# Analog_Modulation.net
KiCad netlist of a schematic drawn in Altium Designer
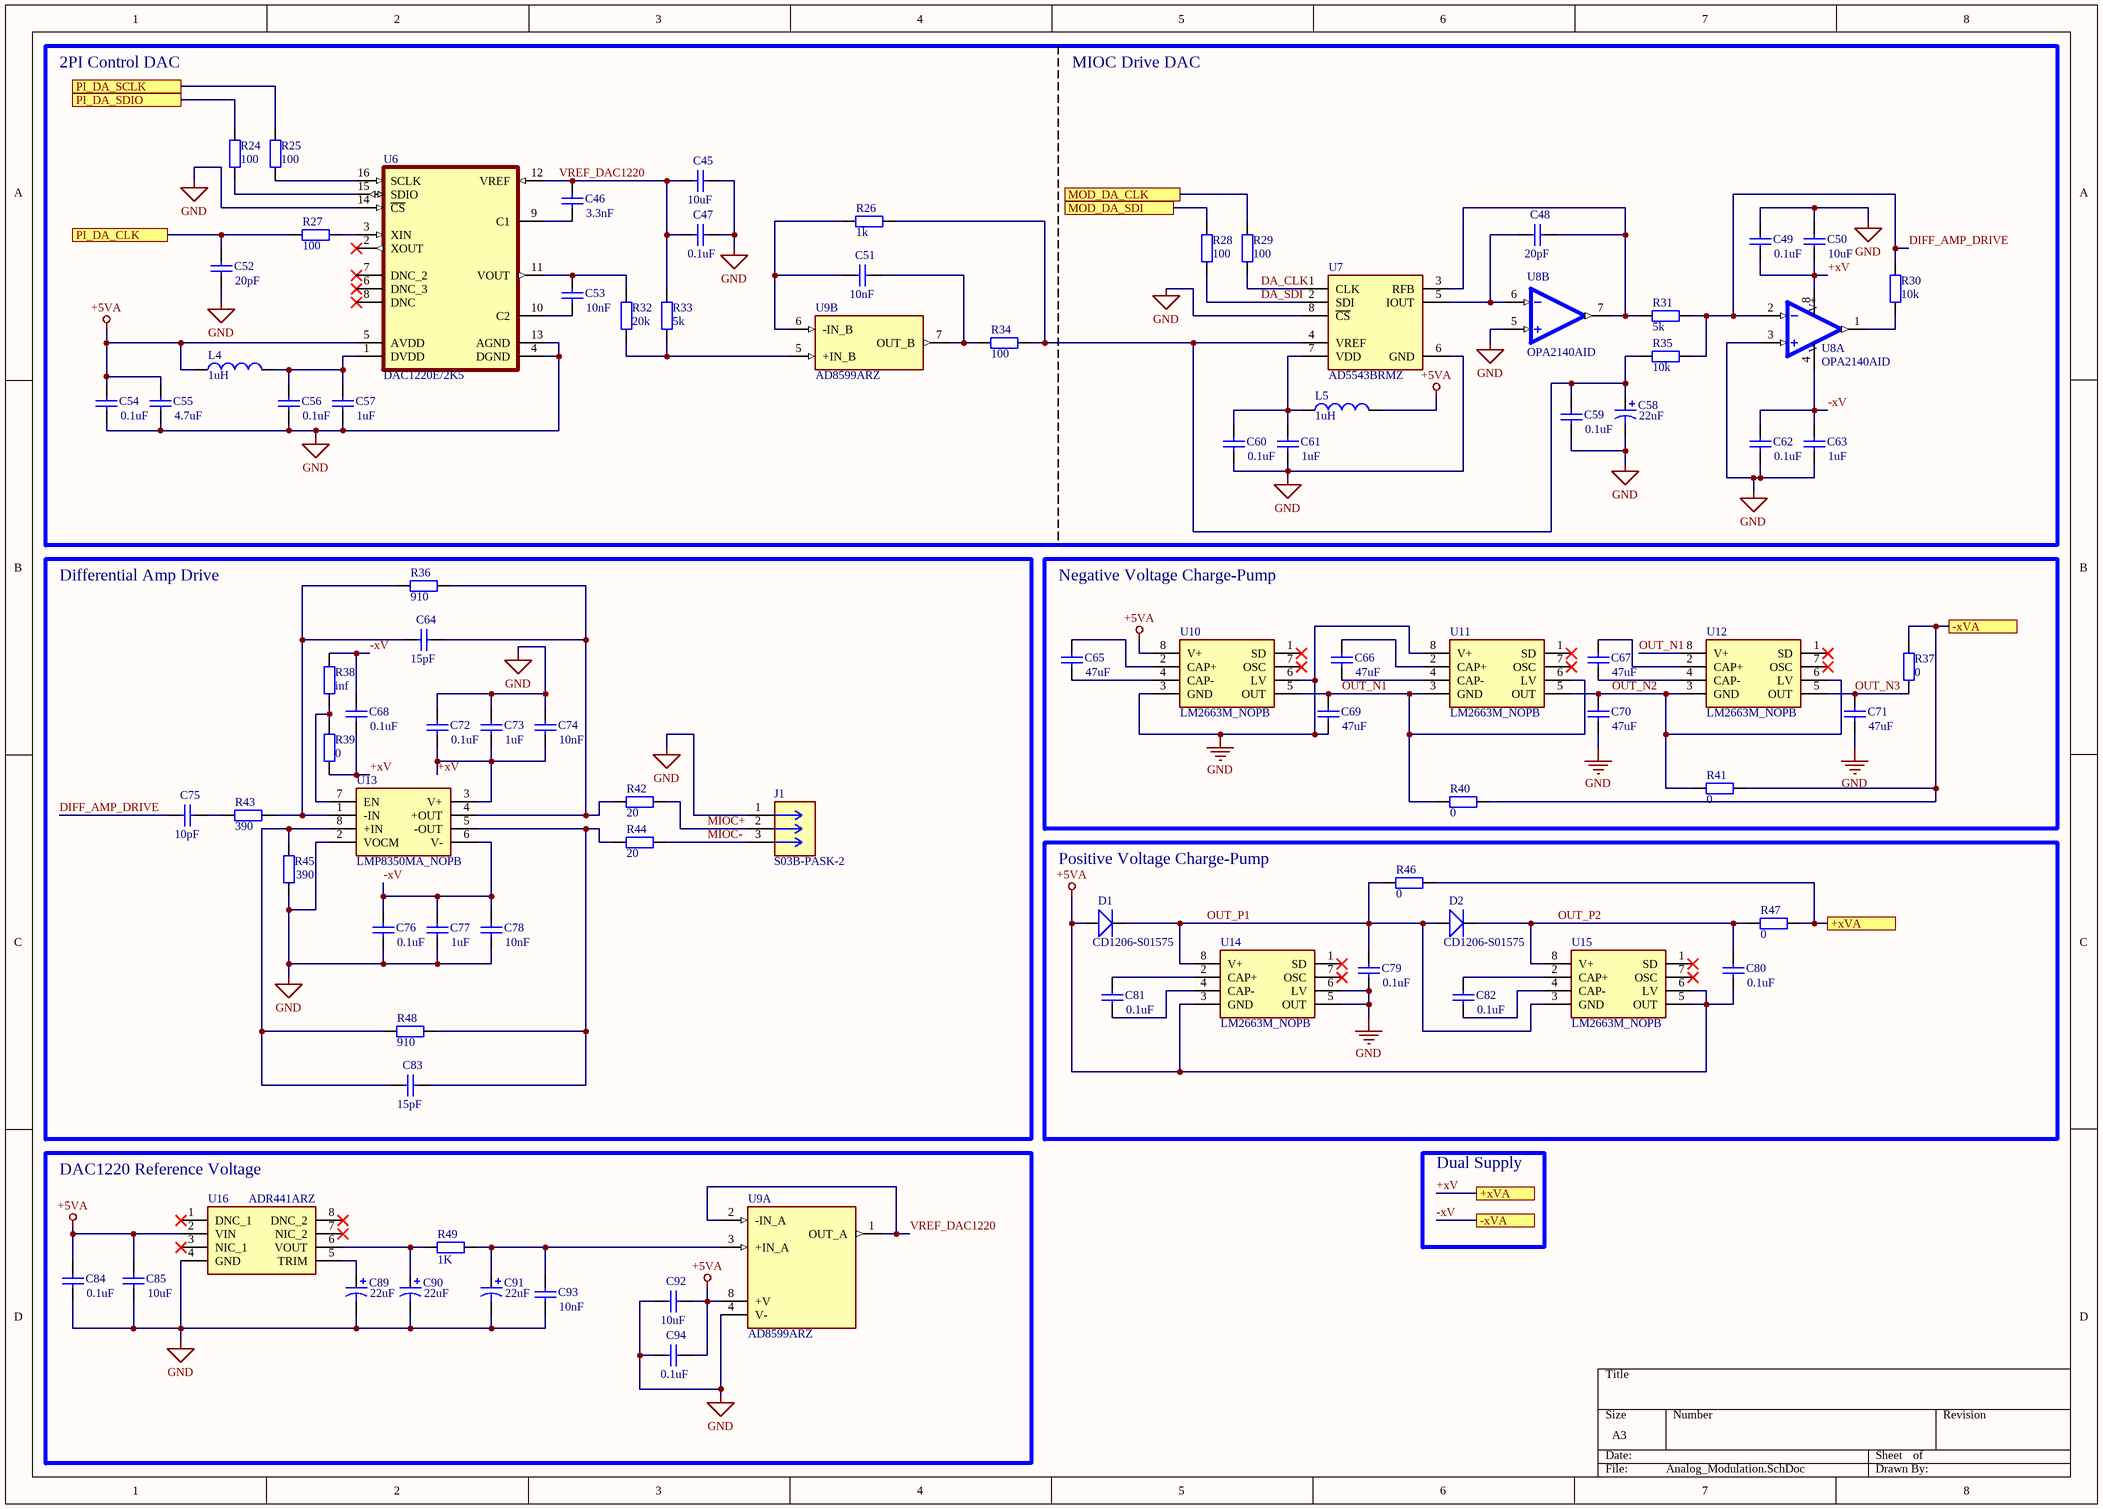
[diagram p0: Analog_Modulation.SchDoc]

(export (version "E")
  (design (tool "Eeschema 10.0.6"))
  (components
    (comp (ref "C45")
      (value "10uF")
      (footprint "CC_0805")
      (description "Capacitor")
      (fields (field (name "Comment") "Cap") (field (name "PUBLISHER") "Altium Limited"))
      (libsource (lib "Miscellaneous Devices") (part "Cap"))
    )
    (comp (ref "C46")
      (value "3.3nF")
      (footprint "CC_0805")
      (description "Capacitor")
      (fields (field (name "Comment") "Cap") (field (name "PUBLISHER") "Altium Limited"))
      (libsource (lib "Miscellaneous Devices") (part "Cap"))
    )
    (comp (ref "C47")
      (value "0.1uF")
      (footprint "CC_0805")
      (description "Capacitor")
      (fields (field (name "Comment") "Cap") (field (name "PUBLISHER") "Altium Limited"))
      (libsource (lib "Miscellaneous Devices") (part "Cap"))
    )
    (comp (ref "C48")
      (value "20pF")
      (footprint "CC_0805")
      (description "Capacitor")
      (fields (field (name "Comment") "Cap") (field (name "PUBLISHER") "Altium Limited"))
      (libsource (lib "Miscellaneous Devices") (part "Cap"))
    )
    (comp (ref "C49")
      (value "0.1uF")
      (footprint "CC_0805")
      (description "Capacitor")
      (fields (field (name "Comment") "Cap") (field (name "PUBLISHER") "Altium Limited"))
      (libsource (lib "Miscellaneous Devices") (part "Cap"))
    )
    (comp (ref "C50")
      (value "10uF")
      (footprint "CC_0805")
      (description "Capacitor")
      (fields (field (name "Comment") "Cap") (field (name "PUBLISHER") "Altium Limited"))
      (libsource (lib "Miscellaneous Devices") (part "Cap"))
    )
    (comp (ref "C51")
      (value "10nF")
      (footprint "CC_0805")
      (description "Capacitor")
      (fields (field (name "Comment") "Cap") (field (name "PUBLISHER") "Altium Limited"))
      (libsource (lib "Miscellaneous Devices") (part "Cap"))
    )
    (comp (ref "C52")
      (value "20pF")
      (footprint "CC_0805")
      (description "Capacitor")
      (fields (field (name "Comment") "Cap") (field (name "PUBLISHER") "Altium Limited"))
      (libsource (lib "Miscellaneous Devices") (part "Cap"))
    )
    (comp (ref "C53")
      (value "10nF")
      (footprint "CC_0805")
      (description "Capacitor")
      (fields (field (name "Comment") "Cap") (field (name "PUBLISHER") "Altium Limited"))
      (libsource (lib "Miscellaneous Devices") (part "Cap"))
    )
    (comp (ref "C54")
      (value "0.1uF")
      (footprint "CC_0805")
      (description "Capacitor")
      (fields (field (name "Comment") "Cap") (field (name "PUBLISHER") "Altium Limited"))
      (libsource (lib "Miscellaneous Devices") (part "Cap"))
    )
    (comp (ref "C55")
      (value "4.7uF")
      (footprint "CC_0805")
      (description "Capacitor")
      (fields (field (name "Comment") "Cap") (field (name "PUBLISHER") "Altium Limited"))
      (libsource (lib "Miscellaneous Devices") (part "Cap"))
    )
    (comp (ref "C56")
      (value "0.1uF")
      (footprint "CC_0805")
      (description "Capacitor")
      (fields (field (name "Comment") "Cap") (field (name "PUBLISHER") "Altium Limited"))
      (libsource (lib "Miscellaneous Devices") (part "Cap"))
    )
    (comp (ref "C57")
      (value "1uF")
      (footprint "CC_0805")
      (description "Capacitor")
      (fields (field (name "Comment") "Cap") (field (name "PUBLISHER") "Altium Limited"))
      (libsource (lib "Miscellaneous Devices") (part "Cap"))
    )
    (comp (ref "C58")
      (value "22uF")
      (footprint "CC_0805")
      (description "Polarized Capacitor (Radial)")
      (fields (field (name "Comment") "Cap Pol1") (field (name "PUBLISHER") "Altium Limited"))
      (libsource (lib "Miscellaneous Devices") (part "Cap Pol1"))
    )
    (comp (ref "C59")
      (value "0.1uF")
      (footprint "CC_0805")
      (description "Capacitor")
      (fields (field (name "Comment") "Cap") (field (name "PUBLISHER") "Altium Limited"))
      (libsource (lib "Miscellaneous Devices") (part "Cap"))
    )
    (comp (ref "C60")
      (value "0.1uF")
      (footprint "CC_0805")
      (description "Capacitor")
      (fields (field (name "Comment") "Cap") (field (name "PUBLISHER") "Altium Limited"))
      (libsource (lib "Miscellaneous Devices") (part "Cap"))
    )
    (comp (ref "C61")
      (value "1uF")
      (footprint "CC_0805")
      (description "Capacitor")
      (fields (field (name "Comment") "Cap") (field (name "PUBLISHER") "Altium Limited"))
      (libsource (lib "Miscellaneous Devices") (part "Cap"))
    )
    (comp (ref "C62")
      (value "0.1uF")
      (footprint "CC_0805")
      (description "Capacitor")
      (fields (field (name "Comment") "Cap") (field (name "PUBLISHER") "Altium Limited"))
      (libsource (lib "Miscellaneous Devices") (part "Cap"))
    )
    (comp (ref "C63")
      (value "1uF")
      (footprint "CC_0805")
      (description "Capacitor")
      (fields (field (name "Comment") "Cap") (field (name "PUBLISHER") "Altium Limited"))
      (libsource (lib "Miscellaneous Devices") (part "Cap"))
    )
    (comp (ref "C64")
      (value "15pF")
      (footprint "CC_0805")
      (description "Capacitor")
      (fields (field (name "Comment") "Cap") (field (name "PUBLISHER") "Altium Limited"))
      (libsource (lib "Miscellaneous Devices") (part "Cap"))
    )
    (comp (ref "C65")
      (value "47uF")
      (footprint "CC_0805")
      (description "Capacitor")
      (fields (field (name "Comment") "Cap") (field (name "PUBLISHER") "Altium Limited"))
      (libsource (lib "Miscellaneous Devices") (part "Cap"))
    )
    (comp (ref "C66")
      (value "47uF")
      (footprint "CC_0805")
      (description "Capacitor")
      (fields (field (name "Comment") "Cap") (field (name "PUBLISHER") "Altium Limited"))
      (libsource (lib "Miscellaneous Devices") (part "Cap"))
    )
    (comp (ref "C67")
      (value "47uF")
      (footprint "CC_0805")
      (description "Capacitor")
      (fields (field (name "Comment") "Cap") (field (name "PUBLISHER") "Altium Limited"))
      (libsource (lib "Miscellaneous Devices") (part "Cap"))
    )
    (comp (ref "C68")
      (value "0.1uF")
      (footprint "CC_0805")
      (description "Capacitor")
      (fields (field (name "Comment") "Cap") (field (name "PUBLISHER") "Altium Limited"))
      (libsource (lib "Miscellaneous Devices") (part "Cap"))
    )
    (comp (ref "C69")
      (value "47uF")
      (footprint "CC_0805")
      (description "Capacitor")
      (fields (field (name "Comment") "Cap") (field (name "PUBLISHER") "Altium Limited"))
      (libsource (lib "Miscellaneous Devices") (part "Cap"))
    )
    (comp (ref "C70")
      (value "47uF")
      (footprint "CC_0805")
      (description "Capacitor")
      (fields (field (name "Comment") "Cap") (field (name "PUBLISHER") "Altium Limited"))
      (libsource (lib "Miscellaneous Devices") (part "Cap"))
    )
    (comp (ref "C71")
      (value "47uF")
      (footprint "CC_0805")
      (description "Capacitor")
      (fields (field (name "Comment") "Cap") (field (name "PUBLISHER") "Altium Limited"))
      (libsource (lib "Miscellaneous Devices") (part "Cap"))
    )
    (comp (ref "C72")
      (value "0.1uF")
      (footprint "CC_0805")
      (description "Capacitor")
      (fields (field (name "Comment") "Cap") (field (name "PUBLISHER") "Altium Limited"))
      (libsource (lib "Miscellaneous Devices") (part "Cap"))
    )
    (comp (ref "C73")
      (value "1uF")
      (footprint "CC_0805")
      (description "Capacitor")
      (fields (field (name "Comment") "Cap") (field (name "PUBLISHER") "Altium Limited"))
      (libsource (lib "Miscellaneous Devices") (part "Cap"))
    )
    (comp (ref "C74")
      (value "10nF")
      (footprint "CC_0805")
      (description "Capacitor")
      (fields (field (name "Comment") "Cap") (field (name "PUBLISHER") "Altium Limited"))
      (libsource (lib "Miscellaneous Devices") (part "Cap"))
    )
    (comp (ref "C75")
      (value "10pF")
      (footprint "CC_0805")
      (description "Capacitor")
      (fields (field (name "Comment") "Cap") (field (name "PUBLISHER") "Altium Limited"))
      (libsource (lib "Miscellaneous Devices") (part "Cap"))
    )
    (comp (ref "C76")
      (value "0.1uF")
      (footprint "CC_0805")
      (description "Capacitor")
      (fields (field (name "Comment") "Cap") (field (name "PUBLISHER") "Altium Limited"))
      (libsource (lib "Miscellaneous Devices") (part "Cap"))
    )
    (comp (ref "C77")
      (value "1uF")
      (footprint "CC_0805")
      (description "Capacitor")
      (fields (field (name "Comment") "Cap") (field (name "PUBLISHER") "Altium Limited"))
      (libsource (lib "Miscellaneous Devices") (part "Cap"))
    )
    (comp (ref "C78")
      (value "10nF")
      (footprint "CC_0805")
      (description "Capacitor")
      (fields (field (name "Comment") "Cap") (field (name "PUBLISHER") "Altium Limited"))
      (libsource (lib "Miscellaneous Devices") (part "Cap"))
    )
    (comp (ref "C79")
      (value "0.1uF")
      (footprint "CC_0805")
      (description "Capacitor")
      (fields (field (name "Comment") "Cap") (field (name "PUBLISHER") "Altium Limited"))
      (libsource (lib "Miscellaneous Devices") (part "Cap"))
    )
    (comp (ref "C80")
      (value "0.1uF")
      (footprint "CC_0805")
      (description "Capacitor")
      (fields (field (name "Comment") "Cap") (field (name "PUBLISHER") "Altium Limited"))
      (libsource (lib "Miscellaneous Devices") (part "Cap"))
    )
    (comp (ref "C81")
      (value "0.1uF")
      (footprint "CC_0805")
      (description "Capacitor")
      (fields (field (name "Comment") "Cap") (field (name "PUBLISHER") "Altium Limited"))
      (libsource (lib "Miscellaneous Devices") (part "Cap"))
    )
    (comp (ref "C82")
      (value "0.1uF")
      (footprint "CC_0805")
      (description "Capacitor")
      (fields (field (name "Comment") "Cap") (field (name "PUBLISHER") "Altium Limited"))
      (libsource (lib "Miscellaneous Devices") (part "Cap"))
    )
    (comp (ref "C83")
      (value "15pF")
      (footprint "CC_0805")
      (description "Capacitor")
      (fields (field (name "Comment") "Cap") (field (name "PUBLISHER") "Altium Limited"))
      (libsource (lib "Miscellaneous Devices") (part "Cap"))
    )
    (comp (ref "C84")
      (value "0.1uF")
      (footprint "CC_0805")
      (description "Capacitor")
      (fields (field (name "Comment") "Cap") (field (name "PUBLISHER") "Altium Limited"))
      (libsource (lib "Miscellaneous Devices") (part "Cap"))
    )
    (comp (ref "C85")
      (value "10uF")
      (footprint "CC_0805")
      (description "Capacitor")
      (fields (field (name "Comment") "Cap") (field (name "PUBLISHER") "Altium Limited"))
      (libsource (lib "Miscellaneous Devices") (part "Cap"))
    )
    (comp (ref "C89")
      (value "22uF")
      (footprint "CC_0805")
      (description "Polarized Capacitor (Radial)")
      (fields (field (name "Comment") "Cap Pol1") (field (name "PUBLISHER") "Altium Limited"))
      (libsource (lib "Miscellaneous Devices") (part "Cap Pol1"))
    )
    (comp (ref "C90")
      (value "22uF")
      (footprint "CC_0805")
      (description "Polarized Capacitor (Radial)")
      (fields (field (name "Comment") "Cap Pol1") (field (name "PUBLISHER") "Altium Limited"))
      (libsource (lib "Miscellaneous Devices") (part "Cap Pol1"))
    )
    (comp (ref "C91")
      (value "22uF")
      (footprint "CC_0805")
      (description "Polarized Capacitor (Radial)")
      (fields (field (name "Comment") "Cap Pol1") (field (name "PUBLISHER") "Altium Limited"))
      (libsource (lib "Miscellaneous Devices") (part "Cap Pol1"))
    )
    (comp (ref "C92")
      (value "10uF")
      (footprint "CC_0805")
      (description "Capacitor")
      (fields (field (name "Comment") "Cap") (field (name "PUBLISHER") "Altium Limited"))
      (libsource (lib "Miscellaneous Devices") (part "Cap"))
    )
    (comp (ref "C93")
      (value "10nF")
      (footprint "CC_0805")
      (description "Capacitor")
      (fields (field (name "Comment") "Cap") (field (name "PUBLISHER") "Altium Limited"))
      (libsource (lib "Miscellaneous Devices") (part "Cap"))
    )
    (comp (ref "C94")
      (value "0.1uF")
      (footprint "CC_0805")
      (description "Capacitor")
      (fields (field (name "Comment") "Cap") (field (name "PUBLISHER") "Altium Limited"))
      (libsource (lib "Miscellaneous Devices") (part "Cap"))
    )
    (comp (ref "D1")
      (value "CD1206-S01575")
      (footprint "LED-1206")
      (description "CD1206-S01575, SMT Switching Diode, Vr=75V 150mA, 4ns, 2-Pin 1206 ¦ Bourns CD1206-S01575")
      (fields (field (name "MF") "Bourns"))
      (libsource (lib "Lib_Schematic_Gyro_Single_Axis") (part "CD1206-S01575"))
    )
    (comp (ref "D2")
      (value "CD1206-S01575")
      (footprint "LED-1206")
      (description "CD1206-S01575, SMT Switching Diode, Vr=75V 150mA, 4ns, 2-Pin 1206 ¦ Bourns CD1206-S01575")
      (fields (field (name "MF") "Bourns"))
      (libsource (lib "Lib_Schematic_Gyro_Single_Axis") (part "CD1206-S01575"))
    )
    (comp (ref "J1")
      (value "S03B-PASK-2")
      (footprint "S03B-PASK-2")
      (description "Headers R/A PCB HDR 3P TIN FRICTION LOCK ¦ Molex Incorporated 22-05-3031")
      (fields (field (name "MF") "Molex") (field (name "MP") "22-05-3031"))
      (libsource (lib "Lib_Schematic_IFOG_Interrogator") (part "S03B-PASK-2"))
    )
    (comp (ref "L4")
      (value "1uH")
      (footprint "WE-PMI_0805_H0.5")
      (description "Inductor")
      (fields (field (name "PUBLISHER") "Altium Limited"))
      (libsource (lib "Miscellaneous Devices") (part "Inductor"))
    )
    (comp (ref "L5")
      (value "1uH")
      (footprint "WE-PMI_0805_H0.5")
      (description "Inductor")
      (fields (field (name "PUBLISHER") "Altium Limited"))
      (libsource (lib "Miscellaneous Devices") (part "Inductor"))
    )
    (comp (ref "R24")
      (value "100")
      (footprint "RR_1220")
      (description "Resistor")
      (fields (field (name "Comment") "Res2") (field (name "PUBLISHER") "Altium Limited"))
      (libsource (lib "") (part "Res2_1"))
    )
    (comp (ref "R25")
      (value "100")
      (footprint "RR_1220")
      (description "Resistor")
      (fields (field (name "Comment") "Res2") (field (name "PUBLISHER") "Altium Limited"))
      (libsource (lib "") (part "Res2_1"))
    )
    (comp (ref "R26")
      (value "1k")
      (footprint "RR_1220")
      (description "Resistor")
      (fields (field (name "Comment") "Res2") (field (name "PUBLISHER") "Altium Limited"))
      (libsource (lib "Miscellaneous Devices") (part "Res2"))
    )
    (comp (ref "R27")
      (value "100")
      (footprint "RR_1220")
      (description "Resistor")
      (fields (field (name "Comment") "Res2") (field (name "PUBLISHER") "Altium Limited"))
      (libsource (lib "Miscellaneous Devices") (part "Res2"))
    )
    (comp (ref "R28")
      (value "100")
      (footprint "RR_1220")
      (description "Resistor")
      (fields (field (name "Comment") "Res2") (field (name "PUBLISHER") "Altium Limited"))
      (libsource (lib "") (part "Res2_3"))
    )
    (comp (ref "R29")
      (value "100")
      (footprint "RR_1220")
      (description "Resistor")
      (fields (field (name "Comment") "Res2") (field (name "PUBLISHER") "Altium Limited"))
      (libsource (lib "") (part "Res2_3"))
    )
    (comp (ref "R30")
      (value "10k")
      (footprint "RR_1220")
      (description "Resistor")
      (fields (field (name "Comment") "Res2") (field (name "PUBLISHER") "Altium Limited"))
      (libsource (lib "") (part "Res2_3"))
    )
    (comp (ref "R31")
      (value "5k")
      (footprint "RR_1220")
      (description "Resistor")
      (fields (field (name "Comment") "Res2") (field (name "PUBLISHER") "Altium Limited"))
      (libsource (lib "Miscellaneous Devices") (part "Res2"))
    )
    (comp (ref "R32")
      (value "20k")
      (footprint "RR_1220")
      (description "Resistor")
      (fields (field (name "Comment") "Res2") (field (name "PUBLISHER") "Altium Limited"))
      (libsource (lib "") (part "Res2_1"))
    )
    (comp (ref "R33")
      (value "5k")
      (footprint "RR_1220")
      (description "Resistor")
      (fields (field (name "Comment") "Res2") (field (name "PUBLISHER") "Altium Limited"))
      (libsource (lib "") (part "Res2_1"))
    )
    (comp (ref "R34")
      (value "100")
      (footprint "RR_1220")
      (description "Resistor")
      (fields (field (name "Comment") "Res2") (field (name "PUBLISHER") "Altium Limited"))
      (libsource (lib "Miscellaneous Devices") (part "Res2"))
    )
    (comp (ref "R35")
      (value "10k")
      (footprint "RR_1220")
      (description "Resistor")
      (fields (field (name "Comment") "Res2") (field (name "PUBLISHER") "Altium Limited"))
      (libsource (lib "Miscellaneous Devices") (part "Res2"))
    )
    (comp (ref "R36")
      (value "910")
      (footprint "RR_1220")
      (description "Resistor")
      (fields (field (name "Comment") "Res2") (field (name "PUBLISHER") "Altium Limited"))
      (libsource (lib "Miscellaneous Devices") (part "Res2"))
    )
    (comp (ref "R37")
      (value "0")
      (footprint "RR_1220")
      (description "Resistor")
      (fields (field (name "Comment") "Res2") (field (name "PUBLISHER") "Altium Limited"))
      (libsource (lib "") (part "Res2_3"))
    )
    (comp (ref "R38")
      (value "inf")
      (footprint "RR_1220")
      (description "Resistor")
      (fields (field (name "Comment") "Res2") (field (name "PUBLISHER") "Altium Limited"))
      (libsource (lib "") (part "Res2_3"))
    )
    (comp (ref "R39")
      (value "0")
      (footprint "RR_1220")
      (description "Resistor")
      (fields (field (name "Comment") "Res2") (field (name "PUBLISHER") "Altium Limited"))
      (libsource (lib "") (part "Res2_3"))
    )
    (comp (ref "R40")
      (value "0")
      (footprint "RR_1220")
      (description "Resistor")
      (fields (field (name "Comment") "Res2") (field (name "PUBLISHER") "Altium Limited"))
      (libsource (lib "Miscellaneous Devices") (part "Res2"))
    )
    (comp (ref "R41")
      (value "0")
      (footprint "RR_1220")
      (description "Resistor")
      (fields (field (name "Comment") "Res2") (field (name "PUBLISHER") "Altium Limited"))
      (libsource (lib "Miscellaneous Devices") (part "Res2"))
    )
    (comp (ref "R42")
      (value "20")
      (footprint "RR_1220")
      (description "Resistor")
      (fields (field (name "Comment") "Res2") (field (name "PUBLISHER") "Altium Limited"))
      (libsource (lib "Miscellaneous Devices") (part "Res2"))
    )
    (comp (ref "R43")
      (value "390")
      (footprint "RR_1220")
      (description "Resistor")
      (fields (field (name "Comment") "Res2") (field (name "PUBLISHER") "Altium Limited"))
      (libsource (lib "Miscellaneous Devices") (part "Res2"))
    )
    (comp (ref "R44")
      (value "20")
      (footprint "RR_1220")
      (description "Resistor")
      (fields (field (name "Comment") "Res2") (field (name "PUBLISHER") "Altium Limited"))
      (libsource (lib "Miscellaneous Devices") (part "Res2"))
    )
    (comp (ref "R45")
      (value "390")
      (footprint "RR_1220")
      (description "Resistor")
      (fields (field (name "Comment") "Res2") (field (name "PUBLISHER") "Altium Limited"))
      (libsource (lib "") (part "Res2_3"))
    )
    (comp (ref "R46")
      (value "0")
      (footprint "RR_1220")
      (description "Resistor")
      (fields (field (name "Comment") "Res2") (field (name "PUBLISHER") "Altium Limited"))
      (libsource (lib "Miscellaneous Devices") (part "Res2"))
    )
    (comp (ref "R47")
      (value "0")
      (footprint "RR_1220")
      (description "Resistor")
      (fields (field (name "Comment") "Res2") (field (name "PUBLISHER") "Altium Limited"))
      (libsource (lib "Miscellaneous Devices") (part "Res2"))
    )
    (comp (ref "R48")
      (value "910")
      (footprint "RR_1220")
      (description "Resistor")
      (fields (field (name "Comment") "Res2") (field (name "PUBLISHER") "Altium Limited"))
      (libsource (lib "Miscellaneous Devices") (part "Res2"))
    )
    (comp (ref "R49")
      (value "1K")
      (footprint "RR_1220")
      (description "Resistor")
      (fields (field (name "Comment") "Res2") (field (name "PUBLISHER") "Altium Limited"))
      (libsource (lib "") (part "Res2_2"))
    )
    (comp (ref "U6")
      (value "DAC1220E/2K5")
      (footprint "DAC1220E/2K5")
      (description "Digital-to-Analog Converter")
      (libsource (lib "Lib_Schematic_Gyro_Single_Axis") (part "DAC1220E/2K5"))
    )
    (comp (ref "U7")
      (value "AD5543BRMZ")
      (footprint "AD5543BRMZ")
      (description "AD5543BRMZ, 16-Bit General Purpose DAC 2.47Msps, SPI, 8-Pin MSOP")
      (fields (field (name "MOUSER PART NUMBER") "584-AD5543BRMZ"))
      (libsource (lib "Lib_Schematic_Gyro_Single_Axis") (part "AD5543BRMZ"))
    )
    (comp (ref "U8")
      (value "OPA2140AID")
      (footprint "OPA2140AID")
      (description "Dual-channel, 11-MHz, low-noise 36-V JFET precision operational amplifier with rail-to-rail output")
      (fields (field (name "MF") "Texas Instruments"))
      (libsource (lib "Lib_Schematic_Gyro_Single_Axis") (part "OPA2140AID"))
    )
    (comp (ref "U9")
      (value "AD8599ARZ")
      (footprint "AD8599ARZ")
      (description "Ultralow Distortion, Ultralow Noise Op Amp (Dual)")
      (fields (field (name "MF") "Analog Devices"))
      (libsource (lib "Lib_Schematic_Gyro_Single_Axis") (part "AD8599ARZ"))
    )
    (comp (ref "U10")
      (value "LM2663M_NOPB")
      (footprint "LM2663M_NOPB")
      (description "200mA switched capacitor voltage converter with low current shutdown mode")
      (fields
        (field (name "MANUFACTURER_PART_NUMBER") "LM2663M/NOPB")
        (field (name "MOUSER PART NUMBER") "926-LM2663M/NOPB")
      )
      (libsource (lib "Lib_Schematic_Gyro_Single_Axis") (part "LM2663M_NOPB"))
    )
    (comp (ref "U11")
      (value "LM2663M_NOPB")
      (footprint "LM2663M_NOPB")
      (description "200mA switched capacitor voltage converter with low current shutdown mode")
      (fields
        (field (name "MANUFACTURER_PART_NUMBER") "LM2663M/NOPB")
        (field (name "MOUSER PART NUMBER") "926-LM2663M/NOPB")
      )
      (libsource (lib "Lib_Schematic_Gyro_Single_Axis") (part "LM2663M_NOPB"))
    )
    (comp (ref "U12")
      (value "LM2663M_NOPB")
      (footprint "LM2663M_NOPB")
      (description "200mA switched capacitor voltage converter with low current shutdown mode")
      (fields
        (field (name "MANUFACTURER_PART_NUMBER") "LM2663M/NOPB")
        (field (name "MOUSER PART NUMBER") "926-LM2663M/NOPB")
      )
      (libsource (lib "Lib_Schematic_Gyro_Single_Axis") (part "LM2663M_NOPB"))
    )
    (comp (ref "U13")
      (value "LMP8350MA_NOPB")
      (footprint "LMP8350MA_NOPB")
      (description "Ultra Low Distortion Fully Differential Precision ADC Driver with Selectable Power Modes")
      (fields
        (field (name "MANUFACTURER_PART_NUMBER") "LMP8350MA/NOPB")
        (field (name "MOUSER PART NUMBER") "926-LMP8350MA/NOPB")
      )
      (libsource (lib "Lib_Schematic_Gyro_Single_Axis") (part "LMP8350MA_NOPB"))
    )
    (comp (ref "U14")
      (value "LM2663M_NOPB")
      (footprint "LM2663M_NOPB")
      (description "200mA switched capacitor voltage converter with low current shutdown mode")
      (fields
        (field (name "MANUFACTURER_PART_NUMBER") "LM2663M/NOPB")
        (field (name "MOUSER PART NUMBER") "926-LM2663M/NOPB")
      )
      (libsource (lib "Lib_Schematic_Gyro_Single_Axis") (part "LM2663M_NOPB"))
    )
    (comp (ref "U15")
      (value "LM2663M_NOPB")
      (footprint "LM2663M_NOPB")
      (description "200mA switched capacitor voltage converter with low current shutdown mode")
      (fields
        (field (name "MANUFACTURER_PART_NUMBER") "LM2663M/NOPB")
        (field (name "MOUSER PART NUMBER") "926-LM2663M/NOPB")
      )
      (libsource (lib "Lib_Schematic_Gyro_Single_Axis") (part "LM2663M_NOPB"))
    )
    (comp (ref "U16")
      (value "ADR441ARZ")
      (footprint "SOIC127P600X175-8N")
      (description "Series Voltage Reference IC Fixed 2.5V V +/-0.12% 10 mA 8-SOIC")
      (fields (field (name "MOUSER PART NUMBER") "584-ADR441ARZ"))
      (libsource (lib "Lib_Schematic_Gyro_Single_Axis") (part "ADR441ARZ"))
    )
  )
  (nets
    (net (code "1") (name "+5VA") (class "Default")
      (node (ref "C54") (pin "1") (pinfunction "1_1") (pintype "passive"))
      (node (ref "C55") (pin "1") (pinfunction "1_1") (pintype "passive"))
      (node (ref "C80") (pin "2") (pinfunction "2_2") (pintype "passive"))
      (node (ref "C84") (pin "2") (pinfunction "2_2") (pintype "passive"))
      (node (ref "C85") (pin "2") (pinfunction "2_2") (pintype "passive"))
      (node (ref "C92") (pin "1") (pinfunction "1_1") (pintype "passive"))
      (node (ref "C94") (pin "1") (pinfunction "1_1") (pintype "passive"))
      (node (ref "D1") (pin "POS") (pinfunction "POS_POS") (pintype "passive"))
      (node (ref "L4") (pin "1") (pinfunction "1_1") (pintype "passive"))
      (node (ref "L5") (pin "2") (pinfunction "2_2") (pintype "passive"))
      (node (ref "U10") (pin "8") (pinfunction "V+_8") (pintype "passive"))
      (node (ref "U14") (pin "3") (pinfunction "GND_3") (pintype "passive"))
      (node (ref "U15") (pin "5") (pinfunction "OUT_5") (pintype "passive"))
      (node (ref "U15") (pin "6") (pinfunction "LV_6") (pintype "passive"))
      (node (ref "U16") (pin "2") (pinfunction "VIN_2") (pintype "passive"))
      (node (ref "U6") (pin "5") (pinfunction "AVDD_5") (pintype "power_in"))
      (node (ref "U9") (pin "8") (pinfunction "+V_8") (pintype "power_in"))
    )
    (net (code "2") (name "/+xV") (class "Default")
      (node (ref "C49") (pin "2") (pinfunction "2_2") (pintype "passive"))
      (node (ref "C50") (pin "2") (pinfunction "2_2") (pintype "passive"))
      (node (ref "C68") (pin "2") (pinfunction "2_2") (pintype "passive"))
      (node (ref "C72") (pin "2") (pinfunction "2_2") (pintype "passive"))
      (node (ref "C73") (pin "2") (pinfunction "2_2") (pintype "passive"))
      (node (ref "C74") (pin "2") (pinfunction "2_2") (pintype "passive"))
      (node (ref "R39") (pin "2") (pinfunction "2_2") (pintype "passive"))
      (node (ref "R46") (pin "1") (pinfunction "1_1") (pintype "passive"))
      (node (ref "R47") (pin "1") (pinfunction "1_1") (pintype "passive"))
      (node (ref "U13") (pin "3") (pinfunction "V+_3") (pintype "passive"))
      (node (ref "U8") (pin "8") (pinfunction "V+_8") (pintype "power_in"))
    )
    (net (code "3") (name "/-xV") (class "Default")
      (node (ref "C62") (pin "1") (pinfunction "1_1") (pintype "passive"))
      (node (ref "C63") (pin "1") (pinfunction "1_1") (pintype "passive"))
      (node (ref "C68") (pin "1") (pinfunction "1_1") (pintype "passive"))
      (node (ref "C76") (pin "1") (pinfunction "1_1") (pintype "passive"))
      (node (ref "C77") (pin "1") (pinfunction "1_1") (pintype "passive"))
      (node (ref "C78") (pin "1") (pinfunction "1_1") (pintype "passive"))
      (node (ref "R37") (pin "1") (pinfunction "1_1") (pintype "passive"))
      (node (ref "R38") (pin "1") (pinfunction "1_1") (pintype "passive"))
      (node (ref "R40") (pin "1") (pinfunction "1_1") (pintype "passive"))
      (node (ref "R41") (pin "1") (pinfunction "1_1") (pintype "passive"))
      (node (ref "U13") (pin "6") (pinfunction "V-_6") (pintype "passive"))
      (node (ref "U8") (pin "4") (pinfunction "V-_4") (pintype "power_in"))
    )
    (net (code "4") (name "/DA_CLK") (class "Default")
      (node (ref "R29") (pin "2") (pinfunction "2_2") (pintype "passive"))
      (node (ref "U7") (pin "1") (pinfunction "CLK_1") (pintype "passive"))
    )
    (net (code "5") (name "/DA_SDI") (class "Default")
      (node (ref "R28") (pin "2") (pinfunction "2_2") (pintype "passive"))
      (node (ref "U7") (pin "2") (pinfunction "SDI_2") (pintype "passive"))
    )
    (net (code "6") (name "/DIFF_AMP_DRIVE") (class "Default")
      (node (ref "C75") (pin "2") (pinfunction "2_2") (pintype "passive"))
      (node (ref "R30") (pin "1") (pinfunction "1_1") (pintype "passive"))
      (node (ref "R31") (pin "1") (pinfunction "1_1") (pintype "passive"))
      (node (ref "R35") (pin "1") (pinfunction "1_1") (pintype "passive"))
      (node (ref "U8") (pin "2") (pinfunction "-INA_2") (pintype "input"))
    )
    (net (code "7") (name "/MIOC+") (class "Default")
      (node (ref "J1") (pin "2") (pinfunction "2_2") (pintype "passive"))
      (node (ref "R42") (pin "1") (pinfunction "1_1") (pintype "passive"))
    )
    (net (code "8") (name "/MIOC-") (class "Default")
      (node (ref "J1") (pin "3") (pinfunction "3_3") (pintype "passive"))
      (node (ref "R44") (pin "1") (pinfunction "1_1") (pintype "passive"))
    )
    (net (code "9") (name "/MOD_DA_CLK") (class "Default")
      (node (ref "R29") (pin "1") (pinfunction "1_1") (pintype "passive"))
    )
    (net (code "10") (name "/MOD_DA_SDI") (class "Default")
      (node (ref "R28") (pin "1") (pinfunction "1_1") (pintype "passive"))
    )
    (net (code "11") (name "/OUT_N1") (class "Default")
      (node (ref "C69") (pin "1") (pinfunction "1_1") (pintype "passive"))
      (node (ref "R40") (pin "2") (pinfunction "2_2") (pintype "passive"))
      (node (ref "U10") (pin "5") (pinfunction "OUT_5") (pintype "passive"))
      (node (ref "U11") (pin "3") (pinfunction "GND_3") (pintype "passive"))
      (node (ref "U11") (pin "6") (pinfunction "LV_6") (pintype "passive"))
      (node (ref "U12") (pin "8") (pinfunction "V+_8") (pintype "passive"))
    )
    (net (code "12") (name "/OUT_N2") (class "Default")
      (node (ref "C70") (pin "1") (pinfunction "1_1") (pintype "passive"))
      (node (ref "R41") (pin "2") (pinfunction "2_2") (pintype "passive"))
      (node (ref "U11") (pin "5") (pinfunction "OUT_5") (pintype "passive"))
      (node (ref "U12") (pin "3") (pinfunction "GND_3") (pintype "passive"))
      (node (ref "U12") (pin "6") (pinfunction "LV_6") (pintype "passive"))
    )
    (net (code "13") (name "/OUT_N3") (class "Default")
      (node (ref "C71") (pin "1") (pinfunction "1_1") (pintype "passive"))
      (node (ref "R37") (pin "2") (pinfunction "2_2") (pintype "passive"))
      (node (ref "U12") (pin "5") (pinfunction "OUT_5") (pintype "passive"))
    )
    (net (code "14") (name "/OUT_P1") (class "Default")
      (node (ref "C79") (pin "1") (pinfunction "1_1") (pintype "passive"))
      (node (ref "D1") (pin "NEG") (pinfunction "NEG_NEG") (pintype "passive"))
      (node (ref "D2") (pin "POS") (pinfunction "POS_POS") (pintype "passive"))
      (node (ref "R46") (pin "2") (pinfunction "2_2") (pintype "passive"))
      (node (ref "U14") (pin "8") (pinfunction "V+_8") (pintype "passive"))
      (node (ref "U15") (pin "3") (pinfunction "GND_3") (pintype "passive"))
    )
    (net (code "15") (name "/OUT_P2") (class "Default")
      (node (ref "C80") (pin "1") (pinfunction "1_1") (pintype "passive"))
      (node (ref "D2") (pin "NEG") (pinfunction "NEG_NEG") (pintype "passive"))
      (node (ref "R47") (pin "2") (pinfunction "2_2") (pintype "passive"))
      (node (ref "U15") (pin "8") (pinfunction "V+_8") (pintype "passive"))
    )
    (net (code "16") (name "/PI_DA_CLK") (class "Default")
      (node (ref "C52") (pin "1") (pinfunction "1_1") (pintype "passive"))
      (node (ref "R27") (pin "2") (pinfunction "2_2") (pintype "passive"))
    )
    (net (code "17") (name "/PI_DA_SCLK") (class "Default")
      (node (ref "R25") (pin "2") (pinfunction "2_2") (pintype "passive"))
    )
    (net (code "18") (name "/PI_DA_SDIO") (class "Default")
      (node (ref "R24") (pin "2") (pinfunction "2_2") (pintype "passive"))
    )
    (net (code "19") (name "/VREF_DAC1220") (class "Default")
      (node (ref "C45") (pin "2") (pinfunction "2_2") (pintype "passive"))
      (node (ref "C46") (pin "1") (pinfunction "1_1") (pintype "passive"))
      (node (ref "C47") (pin "2") (pinfunction "2_2") (pintype "passive"))
      (node (ref "R33") (pin "2") (pinfunction "2_2") (pintype "passive"))
      (node (ref "U6") (pin "12") (pinfunction "VREF_12") (pintype "input"))
      (node (ref "U9") (pin "1") (pinfunction "OUT_A_1") (pintype "output"))
      (node (ref "U9") (pin "2") (pinfunction "-IN_A_2") (pintype "input"))
    )
    (net (code "20") (name "GND") (class "Default")
      (node (ref "C45") (pin "1") (pinfunction "1_1") (pintype "passive"))
      (node (ref "C47") (pin "1") (pinfunction "1_1") (pintype "passive"))
      (node (ref "C49") (pin "1") (pinfunction "1_1") (pintype "passive"))
      (node (ref "C50") (pin "1") (pinfunction "1_1") (pintype "passive"))
      (node (ref "C52") (pin "2") (pinfunction "2_2") (pintype "passive"))
      (node (ref "C54") (pin "2") (pinfunction "2_2") (pintype "passive"))
      (node (ref "C55") (pin "2") (pinfunction "2_2") (pintype "passive"))
      (node (ref "C56") (pin "2") (pinfunction "2_2") (pintype "passive"))
      (node (ref "C57") (pin "2") (pinfunction "2_2") (pintype "passive"))
      (node (ref "C58") (pin "2") (pinfunction "2_2") (pintype "passive"))
      (node (ref "C59") (pin "1") (pinfunction "1_1") (pintype "passive"))
      (node (ref "C60") (pin "2") (pinfunction "2_2") (pintype "passive"))
      (node (ref "C61") (pin "2") (pinfunction "2_2") (pintype "passive"))
      (node (ref "C62") (pin "2") (pinfunction "2_2") (pintype "passive"))
      (node (ref "C63") (pin "2") (pinfunction "2_2") (pintype "passive"))
      (node (ref "C69") (pin "2") (pinfunction "2_2") (pintype "passive"))
      (node (ref "C70") (pin "2") (pinfunction "2_2") (pintype "passive"))
      (node (ref "C71") (pin "2") (pinfunction "2_2") (pintype "passive"))
      (node (ref "C72") (pin "1") (pinfunction "1_1") (pintype "passive"))
      (node (ref "C73") (pin "1") (pinfunction "1_1") (pintype "passive"))
      (node (ref "C74") (pin "1") (pinfunction "1_1") (pintype "passive"))
      (node (ref "C76") (pin "2") (pinfunction "2_2") (pintype "passive"))
      (node (ref "C77") (pin "2") (pinfunction "2_2") (pintype "passive"))
      (node (ref "C78") (pin "2") (pinfunction "2_2") (pintype "passive"))
      (node (ref "C79") (pin "2") (pinfunction "2_2") (pintype "passive"))
      (node (ref "C84") (pin "1") (pinfunction "1_1") (pintype "passive"))
      (node (ref "C85") (pin "1") (pinfunction "1_1") (pintype "passive"))
      (node (ref "C89") (pin "2") (pinfunction "2_2") (pintype "passive"))
      (node (ref "C90") (pin "2") (pinfunction "2_2") (pintype "passive"))
      (node (ref "C91") (pin "2") (pinfunction "2_2") (pintype "passive"))
      (node (ref "C92") (pin "2") (pinfunction "2_2") (pintype "passive"))
      (node (ref "C93") (pin "1") (pinfunction "1_1") (pintype "passive"))
      (node (ref "C94") (pin "2") (pinfunction "2_2") (pintype "passive"))
      (node (ref "J1") (pin "1") (pinfunction "1_1") (pintype "passive"))
      (node (ref "R45") (pin "2") (pinfunction "2_2") (pintype "passive"))
      (node (ref "U10") (pin "3") (pinfunction "GND_3") (pintype "passive"))
      (node (ref "U10") (pin "6") (pinfunction "LV_6") (pintype "passive"))
      (node (ref "U11") (pin "8") (pinfunction "V+_8") (pintype "passive"))
      (node (ref "U13") (pin "2") (pinfunction "VOCM_2") (pintype "passive"))
      (node (ref "U14") (pin "5") (pinfunction "OUT_5") (pintype "passive"))
      (node (ref "U14") (pin "6") (pinfunction "LV_6") (pintype "passive"))
      (node (ref "U16") (pin "4") (pinfunction "GND_4") (pintype "passive"))
      (node (ref "U6") (pin "13") (pinfunction "AGND_13") (pintype "passive"))
      (node (ref "U6") (pin "14") (pinfunction "~{CS}_14") (pintype "input"))
      (node (ref "U6") (pin "4") (pinfunction "DGND_4") (pintype "passive"))
      (node (ref "U7") (pin "6") (pinfunction "GND_6") (pintype "passive"))
      (node (ref "U7") (pin "8") (pinfunction "~{CS}_8") (pintype "passive"))
      (node (ref "U8") (pin "3") (pinfunction "+INA_3") (pintype "input"))
      (node (ref "U8") (pin "5") (pinfunction "+INB_5") (pintype "input"))
      (node (ref "U9") (pin "4") (pinfunction "V-_4") (pintype "power_in"))
    )
    (net (code "21") (name "Net-(C75-Pad1)") (class "Default")
      (node (ref "C75") (pin "1") (pinfunction "1_1") (pintype "passive"))
      (node (ref "R43") (pin "2") (pinfunction "2_2") (pintype "passive"))
    )
    (net (code "22") (name "Net-(U6-C1)") (class "Default")
      (node (ref "C46") (pin "2") (pinfunction "2_2") (pintype "passive"))
      (node (ref "U6") (pin "9") (pinfunction "C1_9") (pintype "passive"))
    )
    (net (code "23") (name "Net-(U6-C2)") (class "Default")
      (node (ref "C53") (pin "2") (pinfunction "2_2") (pintype "passive"))
      (node (ref "U6") (pin "10") (pinfunction "C2_10") (pintype "passive"))
    )
    (net (code "24") (name "Net-(U6-DVDD)") (class "Default")
      (node (ref "C56") (pin "1") (pinfunction "1_1") (pintype "passive"))
      (node (ref "C57") (pin "1") (pinfunction "1_1") (pintype "passive"))
      (node (ref "L4") (pin "2") (pinfunction "2_2") (pintype "passive"))
      (node (ref "U6") (pin "1") (pinfunction "DVDD_1") (pintype "power_in"))
    )
    (net (code "25") (name "Net-(U6-SCLK)") (class "Default")
      (node (ref "R25") (pin "1") (pinfunction "1_1") (pintype "passive"))
      (node (ref "U6") (pin "16") (pinfunction "SCLK_16") (pintype "input"))
    )
    (net (code "26") (name "Net-(U6-SDIO)") (class "Default")
      (node (ref "R24") (pin "1") (pinfunction "1_1") (pintype "passive"))
      (node (ref "U6") (pin "15") (pinfunction "SDIO_15") (pintype "bidirectional"))
    )
    (net (code "27") (name "Net-(U6-VOUT)") (class "Default")
      (node (ref "C53") (pin "1") (pinfunction "1_1") (pintype "passive"))
      (node (ref "R32") (pin "2") (pinfunction "2_2") (pintype "passive"))
      (node (ref "U6") (pin "11") (pinfunction "VOUT_11") (pintype "output"))
    )
    (net (code "28") (name "Net-(U6-XIN)") (class "Default")
      (node (ref "R27") (pin "1") (pinfunction "1_1") (pintype "passive"))
      (node (ref "U6") (pin "3") (pinfunction "XIN_3") (pintype "input"))
    )
    (net (code "29") (name "Net-(U7-IOUT)") (class "Default")
      (node (ref "C48") (pin "2") (pinfunction "2_2") (pintype "passive"))
      (node (ref "U7") (pin "5") (pinfunction "IOUT_5") (pintype "passive"))
      (node (ref "U8") (pin "6") (pinfunction "-INB_6") (pintype "input"))
    )
    (net (code "30") (name "Net-(U7-RFB)") (class "Default")
      (node (ref "C48") (pin "1") (pinfunction "1_1") (pintype "passive"))
      (node (ref "R31") (pin "2") (pinfunction "2_2") (pintype "passive"))
      (node (ref "U7") (pin "3") (pinfunction "RFB_3") (pintype "passive"))
      (node (ref "U8") (pin "7") (pinfunction "OUTB_7") (pintype "output"))
    )
    (net (code "31") (name "Net-(U7-VDD)") (class "Default")
      (node (ref "C60") (pin "1") (pinfunction "1_1") (pintype "passive"))
      (node (ref "C61") (pin "1") (pinfunction "1_1") (pintype "passive"))
      (node (ref "L5") (pin "1") (pinfunction "1_1") (pintype "passive"))
      (node (ref "U7") (pin "7") (pinfunction "VDD_7") (pintype "passive"))
    )
    (net (code "32") (name "Net-(U7-VREF)") (class "Default")
      (node (ref "C58") (pin "1") (pinfunction "1_1") (pintype "passive"))
      (node (ref "C59") (pin "2") (pinfunction "2_2") (pintype "passive"))
      (node (ref "R26") (pin "1") (pinfunction "1_1") (pintype "passive"))
      (node (ref "R34") (pin "1") (pinfunction "1_1") (pintype "passive"))
      (node (ref "R35") (pin "2") (pinfunction "2_2") (pintype "passive"))
      (node (ref "U7") (pin "4") (pinfunction "VREF_4") (pintype "passive"))
    )
    (net (code "33") (name "Net-(U8A-OUTA)") (class "Default")
      (node (ref "R30") (pin "2") (pinfunction "2_2") (pintype "passive"))
      (node (ref "U8") (pin "1") (pinfunction "OUTA_1") (pintype "output"))
    )
    (net (code "34") (name "Net-(U9A-+IN_A)") (class "Default")
      (node (ref "C91") (pin "1") (pinfunction "1_1") (pintype "passive"))
      (node (ref "C93") (pin "2") (pinfunction "2_2") (pintype "passive"))
      (node (ref "R49") (pin "2") (pinfunction "2_2") (pintype "passive"))
      (node (ref "U9") (pin "3") (pinfunction "+IN_A_3") (pintype "input"))
    )
    (net (code "35") (name "Net-(U9B-+IN_B)") (class "Default")
      (node (ref "R32") (pin "1") (pinfunction "1_1") (pintype "passive"))
      (node (ref "R33") (pin "1") (pinfunction "1_1") (pintype "passive"))
      (node (ref "U9") (pin "5") (pinfunction "+IN_B_5") (pintype "input"))
    )
    (net (code "36") (name "Net-(U9B--IN_B)") (class "Default")
      (node (ref "C51") (pin "2") (pinfunction "2_2") (pintype "passive"))
      (node (ref "R26") (pin "2") (pinfunction "2_2") (pintype "passive"))
      (node (ref "U9") (pin "6") (pinfunction "-IN_B_6") (pintype "input"))
    )
    (net (code "37") (name "Net-(U9B-OUT_B)") (class "Default")
      (node (ref "C51") (pin "1") (pinfunction "1_1") (pintype "passive"))
      (node (ref "R34") (pin "2") (pinfunction "2_2") (pintype "passive"))
      (node (ref "U9") (pin "7") (pinfunction "OUT_B_7") (pintype "output"))
    )
    (net (code "38") (name "Net-(U10-CAP+)") (class "Default")
      (node (ref "C65") (pin "1") (pinfunction "1_1") (pintype "passive"))
      (node (ref "U10") (pin "2") (pinfunction "CAP+_2") (pintype "passive"))
    )
    (net (code "39") (name "Net-(U10-CAP-)") (class "Default")
      (node (ref "C65") (pin "2") (pinfunction "2_2") (pintype "passive"))
      (node (ref "U10") (pin "4") (pinfunction "CAP-_4") (pintype "passive"))
    )
    (net (code "40") (name "Net-(U11-CAP+)") (class "Default")
      (node (ref "C66") (pin "1") (pinfunction "1_1") (pintype "passive"))
      (node (ref "U11") (pin "2") (pinfunction "CAP+_2") (pintype "passive"))
    )
    (net (code "41") (name "Net-(U11-CAP-)") (class "Default")
      (node (ref "C66") (pin "2") (pinfunction "2_2") (pintype "passive"))
      (node (ref "U11") (pin "4") (pinfunction "CAP-_4") (pintype "passive"))
    )
    (net (code "42") (name "Net-(U12-CAP+)") (class "Default")
      (node (ref "C67") (pin "1") (pinfunction "1_1") (pintype "passive"))
      (node (ref "U12") (pin "2") (pinfunction "CAP+_2") (pintype "passive"))
    )
    (net (code "43") (name "Net-(U12-CAP-)") (class "Default")
      (node (ref "C67") (pin "2") (pinfunction "2_2") (pintype "passive"))
      (node (ref "U12") (pin "4") (pinfunction "CAP-_4") (pintype "passive"))
    )
    (net (code "44") (name "Net-(U13-+IN)") (class "Default")
      (node (ref "C83") (pin "2") (pinfunction "2_2") (pintype "passive"))
      (node (ref "R45") (pin "1") (pinfunction "1_1") (pintype "passive"))
      (node (ref "R48") (pin "2") (pinfunction "2_2") (pintype "passive"))
      (node (ref "U13") (pin "8") (pinfunction "+IN_8") (pintype "passive"))
    )
    (net (code "45") (name "Net-(U13-+OUT)") (class "Default")
      (node (ref "C64") (pin "1") (pinfunction "1_1") (pintype "passive"))
      (node (ref "R36") (pin "1") (pinfunction "1_1") (pintype "passive"))
      (node (ref "R42") (pin "2") (pinfunction "2_2") (pintype "passive"))
      (node (ref "U13") (pin "4") (pinfunction "+OUT_4") (pintype "passive"))
    )
    (net (code "46") (name "Net-(U13--IN)") (class "Default")
      (node (ref "C64") (pin "2") (pinfunction "2_2") (pintype "passive"))
      (node (ref "R36") (pin "2") (pinfunction "2_2") (pintype "passive"))
      (node (ref "R43") (pin "1") (pinfunction "1_1") (pintype "passive"))
      (node (ref "U13") (pin "1") (pinfunction "-IN_1") (pintype "passive"))
    )
    (net (code "47") (name "Net-(U13--OUT)") (class "Default")
      (node (ref "C83") (pin "1") (pinfunction "1_1") (pintype "passive"))
      (node (ref "R44") (pin "2") (pinfunction "2_2") (pintype "passive"))
      (node (ref "R48") (pin "1") (pinfunction "1_1") (pintype "passive"))
      (node (ref "U13") (pin "5") (pinfunction "-OUT_5") (pintype "passive"))
    )
    (net (code "48") (name "Net-(U13-EN)") (class "Default")
      (node (ref "R38") (pin "2") (pinfunction "2_2") (pintype "passive"))
      (node (ref "R39") (pin "1") (pinfunction "1_1") (pintype "passive"))
      (node (ref "U13") (pin "7") (pinfunction "EN_7") (pintype "passive"))
    )
    (net (code "49") (name "Net-(U14-CAP+)") (class "Default")
      (node (ref "C81") (pin "1") (pinfunction "1_1") (pintype "passive"))
      (node (ref "U14") (pin "2") (pinfunction "CAP+_2") (pintype "passive"))
    )
    (net (code "50") (name "Net-(U14-CAP-)") (class "Default")
      (node (ref "C81") (pin "2") (pinfunction "2_2") (pintype "passive"))
      (node (ref "U14") (pin "4") (pinfunction "CAP-_4") (pintype "passive"))
    )
    (net (code "51") (name "Net-(U15-CAP+)") (class "Default")
      (node (ref "C82") (pin "1") (pinfunction "1_1") (pintype "passive"))
      (node (ref "U15") (pin "2") (pinfunction "CAP+_2") (pintype "passive"))
    )
    (net (code "52") (name "Net-(U15-CAP-)") (class "Default")
      (node (ref "C82") (pin "2") (pinfunction "2_2") (pintype "passive"))
      (node (ref "U15") (pin "4") (pinfunction "CAP-_4") (pintype "passive"))
    )
    (net (code "53") (name "Net-(U16-TRIM)") (class "Default")
      (node (ref "C89") (pin "1") (pinfunction "1_1") (pintype "passive"))
      (node (ref "U16") (pin "5") (pinfunction "TRIM_5") (pintype "passive"))
    )
    (net (code "54") (name "Net-(U16-VOUT)") (class "Default")
      (node (ref "C90") (pin "1") (pinfunction "1_1") (pintype "passive"))
      (node (ref "R49") (pin "1") (pinfunction "1_1") (pintype "passive"))
      (node (ref "U16") (pin "6") (pinfunction "VOUT_6") (pintype "passive"))
    )
    (net (code "55") (name "unconnected-(U6-DNC-Pad8)") (class "Default")
      (node (ref "U6") (pin "8") (pinfunction "DNC_8") (pintype "passive+no_connect"))
    )
    (net (code "56") (name "unconnected-(U6-DNC_2-Pad7)") (class "Default")
      (node (ref "U6") (pin "7") (pinfunction "DNC_2_7") (pintype "passive+no_connect"))
    )
    (net (code "57") (name "unconnected-(U6-DNC_3-Pad6)") (class "Default")
      (node (ref "U6") (pin "6") (pinfunction "DNC_3_6") (pintype "passive+no_connect"))
    )
    (net (code "58") (name "unconnected-(U6-XOUT-Pad2)") (class "Default")
      (node (ref "U6") (pin "2") (pinfunction "XOUT_2") (pintype "output+no_connect"))
    )
    (net (code "59") (name "unconnected-(U10-OSC-Pad7)") (class "Default")
      (node (ref "U10") (pin "7") (pinfunction "OSC_7") (pintype "passive+no_connect"))
    )
    (net (code "60") (name "unconnected-(U10-SD-Pad1)") (class "Default")
      (node (ref "U10") (pin "1") (pinfunction "SD_1") (pintype "passive+no_connect"))
    )
    (net (code "61") (name "unconnected-(U11-OSC-Pad7)") (class "Default")
      (node (ref "U11") (pin "7") (pinfunction "OSC_7") (pintype "passive+no_connect"))
    )
    (net (code "62") (name "unconnected-(U11-SD-Pad1)") (class "Default")
      (node (ref "U11") (pin "1") (pinfunction "SD_1") (pintype "passive+no_connect"))
    )
    (net (code "63") (name "unconnected-(U12-OSC-Pad7)") (class "Default")
      (node (ref "U12") (pin "7") (pinfunction "OSC_7") (pintype "passive+no_connect"))
    )
    (net (code "64") (name "unconnected-(U12-SD-Pad1)") (class "Default")
      (node (ref "U12") (pin "1") (pinfunction "SD_1") (pintype "passive+no_connect"))
    )
    (net (code "65") (name "unconnected-(U14-OSC-Pad7)") (class "Default")
      (node (ref "U14") (pin "7") (pinfunction "OSC_7") (pintype "passive+no_connect"))
    )
    (net (code "66") (name "unconnected-(U14-SD-Pad1)") (class "Default")
      (node (ref "U14") (pin "1") (pinfunction "SD_1") (pintype "passive+no_connect"))
    )
    (net (code "67") (name "unconnected-(U15-OSC-Pad7)") (class "Default")
      (node (ref "U15") (pin "7") (pinfunction "OSC_7") (pintype "passive+no_connect"))
    )
    (net (code "68") (name "unconnected-(U15-SD-Pad1)") (class "Default")
      (node (ref "U15") (pin "1") (pinfunction "SD_1") (pintype "passive+no_connect"))
    )
    (net (code "69") (name "unconnected-(U16-DNC_1-Pad1)") (class "Default")
      (node (ref "U16") (pin "1") (pinfunction "DNC_1_1") (pintype "passive+no_connect"))
    )
    (net (code "70") (name "unconnected-(U16-DNC_2-Pad8)") (class "Default")
      (node (ref "U16") (pin "8") (pinfunction "DNC_2_8") (pintype "passive+no_connect"))
    )
    (net (code "71") (name "unconnected-(U16-NIC_1-Pad3)") (class "Default")
      (node (ref "U16") (pin "3") (pinfunction "NIC_1_3") (pintype "passive+no_connect"))
    )
    (net (code "72") (name "unconnected-(U16-NIC_2-Pad7)") (class "Default")
      (node (ref "U16") (pin "7") (pinfunction "NIC_2_7") (pintype "passive+no_connect"))
    )
  )
)
